# Sensor_Board.net
KiCad netlist of a schematic drawn in Altium Designer
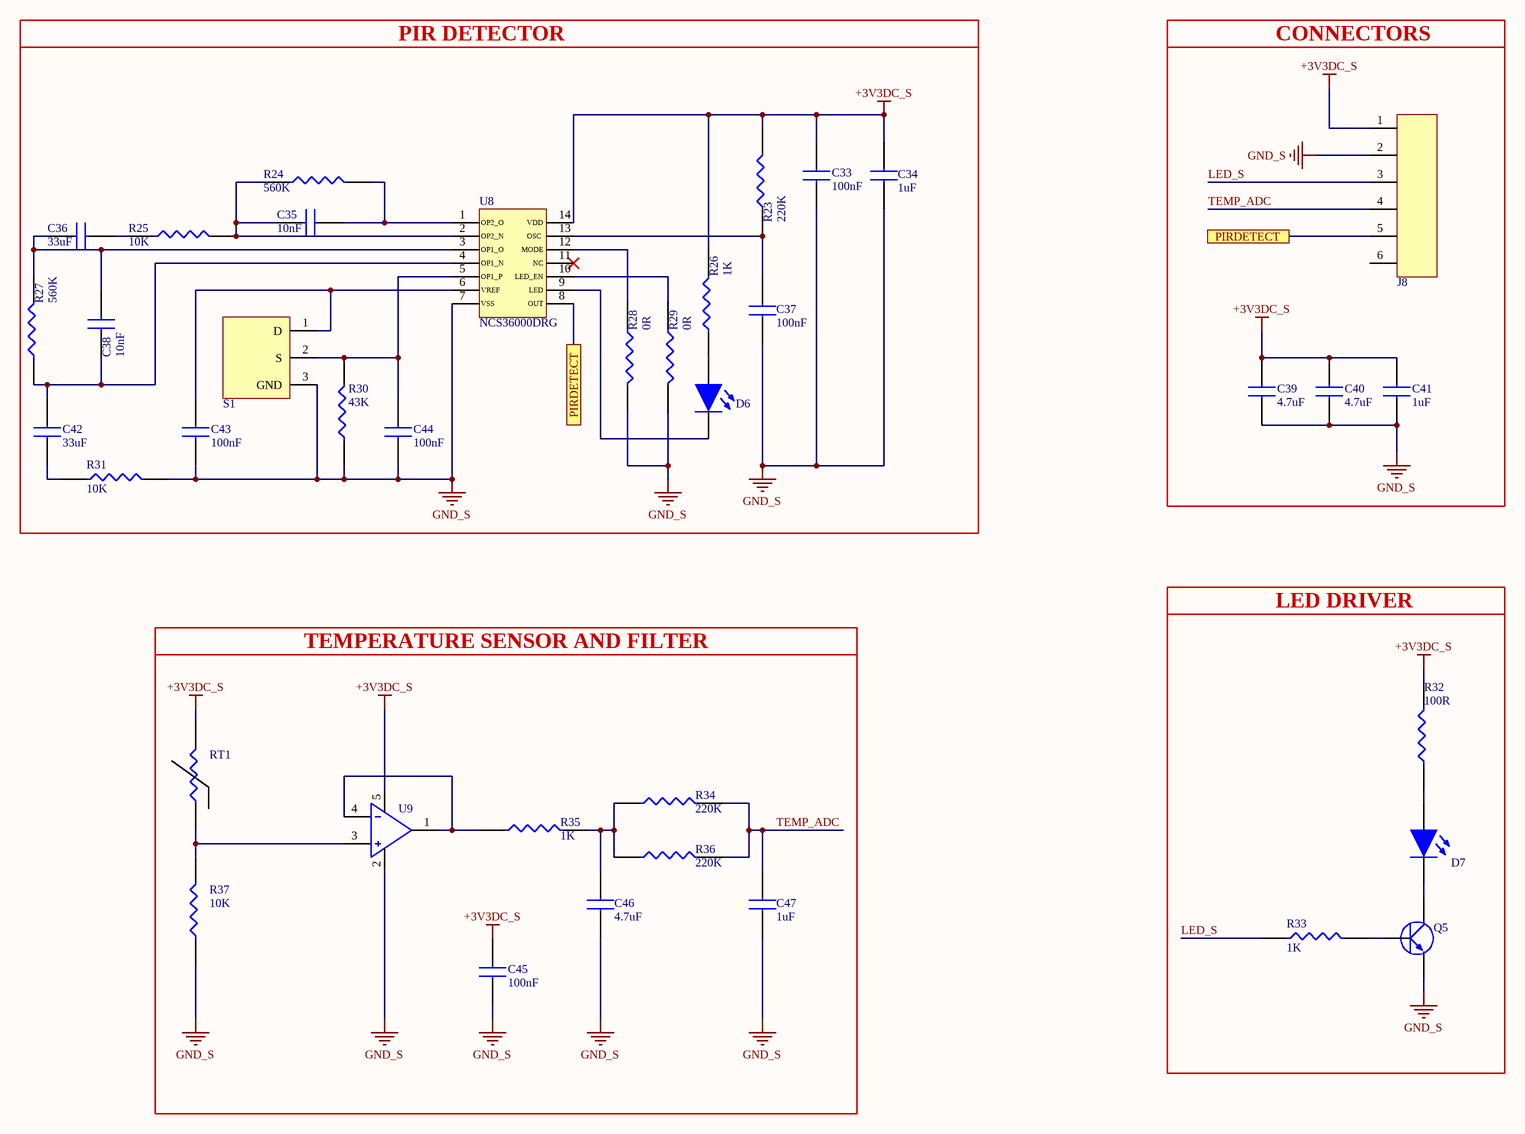
[diagram p0: Sensor Board.SchDoc]

(export (version "E")
  (design (tool "Eeschema 10.0.6"))
  (components
    (comp (ref "C33")
      (value "C0603C104K4RACTU")
      (footprint "CAP_0603")
      (description "Cap Cer 0.1uF 16V X7R 10% SMD 0603 125°C Paper T/R")
      (fields
        (field (name "MANUFACTURER") "KEMET")
        (field (name "TOLERANCE") "10%")
        (field (name "CAPACITANCE") "100nF")
        (field (name "DESIGNED BY") "Onur Karaduman")
      )
      (libsource (lib "Ders1Lib") (part "CAP CER 100nF 0603"))
    )
    (comp (ref "C34")
      (value "CL21B105KBFNNNE")
      (footprint "CAP_0805")
      (description "CAP CER 1UF 50V X7R 0805")
      (fields
        (field (name "MANUFACTURER") "Samsung")
        (field (name "TOLERANCE") "10%")
        (field (name "CAPACITANCE") "1uF")
        (field (name "DESIGNED BY") "Onur Karaduman")
      )
      (libsource (lib "Ders1Lib") (part "CAP CER 1uF 0805"))
    )
    (comp (ref "C35")
      (value "0603B103K160CT")
      (footprint "CAP_0603")
      (description "Multilayer Ceramic Capacitor, 0.01 F, 10%, X7R, 16 V, 0603 [1608 Metric] RoHS Compliant: Yes")
      (fields
        (field (name "MANUFACTURER") "Walsin Technologies")
        (field (name "TOLERANCE") "10%")
        (field (name "CAPACITANCE") "10nF")
        (field (name "DESIGNED BY") "Onur Karaduman")
      )
      (libsource (lib "Ders1Lib") (part "CAP CER 10nF 0603"))
    )
    (comp (ref "C36")
      (value "C3216X5R1E336M160AC")
      (footprint "CAP_1206")
      (description "C Series 1206 33 uF 25 V ±20 % Tolerance X5R SMT Multilayer Ceramic Capacitor")
      (fields
        (field (name "MANUFACTURER") "TDK")
        (field (name "TOLERANCE") "20%")
        (field (name "CAPACITANCE") "33uF")
        (field (name "DESIGNED BY") "Onur Karaduman")
      )
      (libsource (lib "Ders1Lib") (part "CAP CER 33uF 1206"))
    )
    (comp (ref "C37")
      (value "C0603C104K4RACTU")
      (footprint "CAP_0603")
      (description "Cap Cer 0.1uF 16V X7R 10% SMD 0603 125°C Paper T/R")
      (fields
        (field (name "MANUFACTURER") "KEMET")
        (field (name "TOLERANCE") "10%")
        (field (name "CAPACITANCE") "100nF")
        (field (name "DESIGNED BY") "Onur Karaduman")
      )
      (libsource (lib "Ders1Lib") (part "CAP CER 100nF 0603"))
    )
    (comp (ref "C38")
      (value "0603B103K160CT")
      (footprint "CAP_0603")
      (description "Multilayer Ceramic Capacitor, 0.01 F, 10%, X7R, 16 V, 0603 [1608 Metric] RoHS Compliant: Yes")
      (fields
        (field (name "MANUFACTURER") "Walsin Technologies")
        (field (name "TOLERANCE") "10%")
        (field (name "CAPACITANCE") "10nF")
        (field (name "DESIGNED BY") "Onur Karaduman")
      )
      (libsource (lib "Ders1Lib") (part "CAP CER 10nF 0603"))
    )
    (comp (ref "C39")
      (value "CL21A475KAQNNNE")
      (footprint "CAP_0805")
      (description "CAP CER 4.7UF 25V X5R 0805")
      (fields
        (field (name "MANUFACTURER") "Samsung")
        (field (name "TOLERANCE") "10%")
        (field (name "CAPACITANCE") "4.7uF")
        (field (name "DESIGNED BY") "Onur Karaduman")
      )
      (libsource (lib "Ders1Lib") (part "CAP CER 4.7uF 0805"))
    )
    (comp (ref "C40")
      (value "CL21A475KAQNNNE")
      (footprint "CAP_0805")
      (description "CAP CER 4.7UF 25V X5R 0805")
      (fields
        (field (name "MANUFACTURER") "Samsung")
        (field (name "TOLERANCE") "10%")
        (field (name "CAPACITANCE") "4.7uF")
        (field (name "DESIGNED BY") "Onur Karaduman")
      )
      (libsource (lib "Ders1Lib") (part "CAP CER 4.7uF 0805"))
    )
    (comp (ref "C41")
      (value "CL21B105KBFNNNE")
      (footprint "CAP_0805")
      (description "CAP CER 1UF 50V X7R 0805")
      (fields
        (field (name "MANUFACTURER") "Samsung")
        (field (name "TOLERANCE") "10%")
        (field (name "CAPACITANCE") "1uF")
        (field (name "DESIGNED BY") "Onur Karaduman")
      )
      (libsource (lib "Ders1Lib") (part "CAP CER 1uF 0805"))
    )
    (comp (ref "C42")
      (value "C3216X5R1E336M160AC")
      (footprint "CAP_1206")
      (description "C Series 1206 33 uF 25 V ±20 % Tolerance X5R SMT Multilayer Ceramic Capacitor")
      (fields
        (field (name "MANUFACTURER") "TDK")
        (field (name "TOLERANCE") "20%")
        (field (name "CAPACITANCE") "33uF")
        (field (name "DESIGNED BY") "Onur Karaduman")
      )
      (libsource (lib "Ders1Lib") (part "CAP CER 33uF 1206"))
    )
    (comp (ref "C43")
      (value "C0603C104K4RACTU")
      (footprint "CAP_0603")
      (description "Cap Cer 0.1uF 16V X7R 10% SMD 0603 125°C Paper T/R")
      (fields
        (field (name "MANUFACTURER") "KEMET")
        (field (name "TOLERANCE") "10%")
        (field (name "CAPACITANCE") "100nF")
        (field (name "DESIGNED BY") "Onur Karaduman")
      )
      (libsource (lib "Ders1Lib") (part "CAP CER 100nF 0603"))
    )
    (comp (ref "C44")
      (value "C0603C104K4RACTU")
      (footprint "CAP_0603")
      (description "Cap Cer 0.1uF 16V X7R 10% SMD 0603 125°C Paper T/R")
      (fields
        (field (name "MANUFACTURER") "KEMET")
        (field (name "TOLERANCE") "10%")
        (field (name "CAPACITANCE") "100nF")
        (field (name "DESIGNED BY") "Onur Karaduman")
      )
      (libsource (lib "Ders1Lib") (part "CAP CER 100nF 0603"))
    )
    (comp (ref "C45")
      (value "C0603C104K4RACTU")
      (footprint "CAP_0603")
      (description "Cap Cer 0.1uF 16V X7R 10% SMD 0603 125°C Paper T/R")
      (fields
        (field (name "MANUFACTURER") "KEMET")
        (field (name "TOLERANCE") "10%")
        (field (name "CAPACITANCE") "100nF")
        (field (name "DESIGNED BY") "Onur Karaduman")
      )
      (libsource (lib "Ders1Lib") (part "CAP CER 100nF 0603"))
    )
    (comp (ref "C46")
      (value "CL21A475KAQNNNE")
      (footprint "CAP_0805")
      (description "CAP CER 4.7UF 25V X5R 0805")
      (fields
        (field (name "MANUFACTURER") "Samsung")
        (field (name "TOLERANCE") "10%")
        (field (name "CAPACITANCE") "4.7uF")
        (field (name "DESIGNED BY") "Onur Karaduman")
      )
      (libsource (lib "Ders1Lib") (part "CAP CER 4.7uF 0805"))
    )
    (comp (ref "C47")
      (value "CL21B105KBFNNNE")
      (footprint "CAP_0805")
      (description "CAP CER 1UF 50V X7R 0805")
      (fields
        (field (name "MANUFACTURER") "Samsung")
        (field (name "TOLERANCE") "10%")
        (field (name "CAPACITANCE") "1uF")
        (field (name "DESIGNED BY") "Onur Karaduman")
      )
      (libsource (lib "Ders1Lib") (part "CAP CER 1uF 0805"))
    )
    (comp (ref "D6")
      (value "LTST-C171GKT")
      (footprint "LED_GREEN 0805")
      (description "Green 569nm LED Indication - Discrete 2.1V 0805 (2012 Metric)")
      (fields (field (name "MANUFACTURER") "Vishay Lite-On") (field (name "DESIGNED BY") "Onur Karaduman"))
      (libsource (lib "Ders1Lib") (part "LED GREEN 0805"))
    )
    (comp (ref "D7")
      (value "LH R974-LP-1")
      (footprint "LED_0805")
      (description "LED Uni-Color Hyper Red 660nm 2-Pin Chip 0805(2012Metric) T/R")
      (fields (field (name "MANUFACTURER") "Osram Opto") (field (name "DESIGNED BY") "Onur Karaduman"))
      (libsource (lib "Ders1Lib") (part "LED RED 0805"))
    )
    (comp (ref "J8")
      (value "64800611622")
      (footprint "64800611622")
      (description "Conn, Header, 6POS, 1ROW, 1.5MM;")
      (fields (field (name "MANUFACTURER") "Wurth Electronics") (field (name "DESIGNED BY") "Onur Karaduman"))
      (libsource (lib "Ders1Lib") (part "64800611622"))
    )
    (comp (ref "Q5")
      (value "MMBT3904-7-F")
      (footprint "SOT23-F")
      (description "NPN Ic=200mA Vceo=40V hfe=100~300 fT=310MHz P=300mW SOT-23")
      (fields (field (name "MANUFACTURER") "Diodes Zetex") (field (name "DESIGNED BY") "Onur Karaduman"))
      (libsource (lib "Ders1Lib") (part "MMBT3904-7-F"))
    )
    (comp (ref "R23")
      (value "RC0603JR-07220KL")
      (footprint "RES_0603")
      (description "Res Thick Film 0603 220K Ohm 5% 0.1W(1/10W) ±100ppm/C Pad SMD T/R")
      (fields
        (field (name "MANUFACTURER") "Yageo")
        (field (name "TOLERANCE") "5%")
        (field (name "RESISTANCE") "220K")
        (field (name "DESIGNED BY") "Onur Karaduman")
      )
      (libsource (lib "Ders1Lib") (part "RES 220K OHM 0603"))
    )
    (comp (ref "R24")
      (value "RC0603JR-07560KL")
      (footprint "RES_0603")
      (description "Res Thick Film 0603 560K Ohm 5% 0.1W(1/10W) ±100ppm/C Molded SMD Paper T/R")
      (fields
        (field (name "MANUFACTURER") "Yageo")
        (field (name "TOLERANCE") "5%")
        (field (name "RESISTANCE") "560K")
        (field (name "DESIGNED BY") "Onur Karaduman")
      )
      (libsource (lib "Ders1Lib") (part "RES 560K KOHM 0603"))
    )
    (comp (ref "R25")
      (value "RC0603FR-0710KL")
      (footprint "RES_0603")
      (description "RES SMD 10K OHM 1% 1/10W 0603")
      (fields
        (field (name "MANUFACTURER") "Yageo")
        (field (name "TOLERANCE") "1%")
        (field (name "RESISTANCE") "10K")
        (field (name "DESIGNED BY") "Onur Karaduman")
      )
      (libsource (lib "Ders1Lib") (part "RES 10K OHM 0603"))
    )
    (comp (ref "R26")
      (value "RES 1K OHM 0603")
      (footprint "RES_0603")
      (description "Res Thick Film 0603 1K Ohm 1% 0.25W(1/4W) ±100ppm/°C Epoxy Resin Pad SMD Automotive T/R")
      (fields
        (field (name "MANUFACTURER") "Rohm")
        (field (name "MANUFACTURER PART NUMBER") "ESR03EZPF1001")
        (field (name "RESISTANCE") "1K")
        (field (name "DESIGNED BY") "Onur Karaduman")
      )
      (libsource (lib "Ders1Lib") (part "RES 1K OHM 0603"))
    )
    (comp (ref "R27")
      (value "RC0603JR-07560KL")
      (footprint "RES_0603")
      (description "Res Thick Film 0603 560K Ohm 5% 0.1W(1/10W) ±100ppm/C Molded SMD Paper T/R")
      (fields
        (field (name "MANUFACTURER") "Yageo")
        (field (name "TOLERANCE") "5%")
        (field (name "RESISTANCE") "560K")
        (field (name "DESIGNED BY") "Onur Karaduman")
      )
      (libsource (lib "Ders1Lib") (part "RES 560K KOHM 0603"))
    )
    (comp (ref "R28")
      (value "RES 0 OHM 0603")
      (footprint "RES_0603")
      (description "RES SMD 0 OHM JUMPER 1/10W 0603")
      (fields
        (field (name "MANUFACTURER") "Yageo")
        (field (name "MANUFACTURER PART NUMBER") "RC0603JR-070RL")
        (field (name "RESISTANCE") "0R")
        (field (name "DESIGNED BY") "Onur Karaduman")
      )
      (libsource (lib "Ders1Lib") (part "RES 0 OHM 0603"))
    )
    (comp (ref "R29")
      (value "RES 0 OHM 0603")
      (footprint "RES_0603")
      (description "RES SMD 0 OHM JUMPER 1/10W 0603")
      (fields
        (field (name "MANUFACTURER") "Yageo")
        (field (name "MANUFACTURER PART NUMBER") "RC0603JR-070RL")
        (field (name "RESISTANCE") "0R")
        (field (name "DESIGNED BY") "Onur Karaduman")
      )
      (libsource (lib "Ders1Lib") (part "RES 0 OHM 0603"))
    )
    (comp (ref "R30")
      (value "RC0603JR-0743KL")
      (footprint "RES_0603")
      (description "Res Thick Film 0603 43K Ohm 5% 0.1W(1/10W) ±100ppm/°C Pad SMD T/R")
      (fields
        (field (name "MANUFACTURER") "Yageo")
        (field (name "TOLERANCE") "5%")
        (field (name "RESISTANCE") "43K")
        (field (name "DESIGNED BY") "Onur Karaduman")
      )
      (libsource (lib "Ders1Lib") (part "RES 43K OHM 0603"))
    )
    (comp (ref "R31")
      (value "RC0603FR-0710KL")
      (footprint "RES_0603")
      (description "RES SMD 10K OHM 1% 1/10W 0603")
      (fields
        (field (name "MANUFACTURER") "Yageo")
        (field (name "TOLERANCE") "1%")
        (field (name "RESISTANCE") "10K")
        (field (name "DESIGNED BY") "Onur Karaduman")
      )
      (libsource (lib "Ders1Lib") (part "RES 10K OHM 0603"))
    )
    (comp (ref "R32")
      (value "RC0603JR-07100RL")
      (footprint "RES_0603")
      (description "Res Thick Film 0603 100 Ohm 5% 1/10W ±100ppm/°C Molded SMD SMD Paper T/R")
      (fields
        (field (name "MANUFACTURER") "Yageo")
        (field (name "TOLERANCE") "5%")
        (field (name "RESISTANCE") "100R")
        (field (name "DESIGNED BY") "Onur Karaduman")
      )
      (libsource (lib "Ders1Lib") (part "RES 100 OHM 0603"))
    )
    (comp (ref "R33")
      (value "RES 1K OHM 0603")
      (footprint "RES_0603")
      (description "Res Thick Film 0603 1K Ohm 1% 0.25W(1/4W) ±100ppm/°C Epoxy Resin Pad SMD Automotive T/R")
      (fields
        (field (name "MANUFACTURER") "Rohm")
        (field (name "MANUFACTURER PART NUMBER") "ESR03EZPF1001")
        (field (name "RESISTANCE") "1K")
        (field (name "DESIGNED BY") "Onur Karaduman")
      )
      (libsource (lib "Ders1Lib") (part "RES 1K OHM 0603"))
    )
    (comp (ref "R34")
      (value "RC0603JR-07220KL")
      (footprint "RES_0603")
      (description "Res Thick Film 0603 220K Ohm 5% 0.1W(1/10W) ±100ppm/C Pad SMD T/R")
      (fields
        (field (name "MANUFACTURER") "Yageo")
        (field (name "TOLERANCE") "5%")
        (field (name "RESISTANCE") "220K")
        (field (name "DESIGNED BY") "Onur Karaduman")
      )
      (libsource (lib "Ders1Lib") (part "RES 220K OHM 0603"))
    )
    (comp (ref "R35")
      (value "RES 1K OHM 0603")
      (footprint "RES_0603")
      (description "Res Thick Film 0603 1K Ohm 1% 0.25W(1/4W) ±100ppm/°C Epoxy Resin Pad SMD Automotive T/R")
      (fields
        (field (name "MANUFACTURER") "Rohm")
        (field (name "MANUFACTURER PART NUMBER") "ESR03EZPF1001")
        (field (name "RESISTANCE") "1K")
        (field (name "DESIGNED BY") "Onur Karaduman")
      )
      (libsource (lib "Ders1Lib") (part "RES 1K OHM 0603"))
    )
    (comp (ref "R36")
      (value "RC0603JR-07220KL")
      (footprint "RES_0603")
      (description "Res Thick Film 0603 220K Ohm 5% 0.1W(1/10W) ±100ppm/C Pad SMD T/R")
      (fields
        (field (name "MANUFACTURER") "Yageo")
        (field (name "TOLERANCE") "5%")
        (field (name "RESISTANCE") "220K")
        (field (name "DESIGNED BY") "Onur Karaduman")
      )
      (libsource (lib "Ders1Lib") (part "RES 220K OHM 0603"))
    )
    (comp (ref "R37")
      (value "RC0603FR-0710KL")
      (footprint "RES_0603")
      (description "RES SMD 10K OHM 1% 1/10W 0603")
      (fields
        (field (name "MANUFACTURER") "Yageo")
        (field (name "TOLERANCE") "1%")
        (field (name "RESISTANCE") "10K")
        (field (name "DESIGNED BY") "Onur Karaduman")
      )
      (libsource (lib "Ders1Lib") (part "RES 10K OHM 0603"))
    )
    (comp (ref "RT1")
      (value "TFPT1206L1002FM")
      (footprint "TFPT 1206")
      (description "Thermistor PTC 10K Ohm 1% 2-Pin 1206 Surface Mount Solder Pad T/R Automotive")
      (fields (field (name "MANUFACTURER") "Vishay Dale") (field (name "TOLERANCE") "1%"))
      (libsource (lib "Ders1Lib") (part "TFPT1206L1002FM"))
    )
    (comp (ref "S1")
      (value "LHI 878/ 3902")
      (footprint "LHI 878/ 3902")
      (description "Sensor PIR (Passive Infrared) TO-205AA, TO-5-3 Metal Can")
      (fields
        (field (name "MANUFACTURER") "Excelitas")
        (field (name "MANUFACTURER PART NUMBER") "LHI878/3902")
        (field (name "DESIGNED BY") "Onur Karaduman")
      )
      (libsource (lib "Ders1Lib") (part "LHI 878/ 3902"))
    )
    (comp (ref "U8")
      (value "NCS36000DRG")
      (footprint "SOIC 14")
      (description "NCS36000 Series Single 5.75V Passive Infrared Detector Controller (PIR) -SOIC-14")
      (fields (field (name "MANUFACTURER") "ON Semiconductor"))
      (libsource (lib "Ders1Lib") (part "NCS36000DRG"))
    )
    (comp (ref "U9")
      (value "OPA314AIDBVR")
      (footprint "SOT23-5")
      (description "IC OPAMP GP 3MHZ RRO SOT23-5")
      (fields
        (field (name "MANUFACTURER") "Texas Instruments")
        (field (name "DESIGNED  BY") "Onur Karaduman")
      )
      (libsource (lib "Ders1Lib") (part "OPA314AIDBVR"))
    )
  )
  (nets
    (net (code "1") (name "+3V3DC_S") (class "Default")
      (node (ref "C33") (pin "2") (pintype "passive"))
      (node (ref "C34") (pin "2") (pintype "passive"))
      (node (ref "C39") (pin "2") (pintype "passive"))
      (node (ref "C40") (pin "2") (pintype "passive"))
      (node (ref "C41") (pin "2") (pintype "passive"))
      (node (ref "C45") (pin "2") (pintype "passive"))
      (node (ref "J8") (pin "1") (pintype "passive"))
      (node (ref "R23") (pin "2") (pintype "passive"))
      (node (ref "R26") (pin "2") (pintype "passive"))
      (node (ref "R32") (pin "2") (pintype "passive"))
      (node (ref "RT1") (pin "2") (pintype "passive"))
      (node (ref "U8") (pin "14") (pinfunction "VDD_14") (pintype "passive"))
      (node (ref "U9") (pin "5") (pintype "passive"))
    )
    (net (code "2") (name "/LED_S") (class "Default")
      (node (ref "J8") (pin "3") (pintype "passive"))
      (node (ref "R33") (pin "1") (pintype "passive"))
    )
    (net (code "3") (name "/PIRDETECT") (class "Default")
      (node (ref "J8") (pin "5") (pintype "passive"))
      (node (ref "U8") (pin "8") (pinfunction "OUT_8") (pintype "passive"))
    )
    (net (code "4") (name "/TEMP_ADC") (class "Default")
      (node (ref "C47") (pin "2") (pintype "passive"))
      (node (ref "J8") (pin "4") (pintype "passive"))
      (node (ref "R34") (pin "2") (pintype "passive"))
      (node (ref "R36") (pin "2") (pintype "passive"))
    )
    (net (code "5") (name "GND_S") (class "Default")
      (node (ref "C33") (pin "1") (pintype "passive"))
      (node (ref "C34") (pin "1") (pintype "passive"))
      (node (ref "C37") (pin "1") (pintype "passive"))
      (node (ref "C39") (pin "1") (pintype "passive"))
      (node (ref "C40") (pin "1") (pintype "passive"))
      (node (ref "C41") (pin "1") (pintype "passive"))
      (node (ref "C43") (pin "1") (pintype "passive"))
      (node (ref "C44") (pin "1") (pintype "passive"))
      (node (ref "C45") (pin "1") (pintype "passive"))
      (node (ref "C46") (pin "1") (pintype "passive"))
      (node (ref "C47") (pin "1") (pintype "passive"))
      (node (ref "J8") (pin "2") (pintype "passive"))
      (node (ref "Q5") (pin "2") (pinfunction "2_2") (pintype "passive"))
      (node (ref "R28") (pin "2") (pintype "passive"))
      (node (ref "R29") (pin "2") (pintype "passive"))
      (node (ref "R30") (pin "1") (pintype "passive"))
      (node (ref "R31") (pin "2") (pintype "passive"))
      (node (ref "R37") (pin "1") (pintype "passive"))
      (node (ref "S1") (pin "3") (pinfunction "GND_3") (pintype "passive"))
      (node (ref "U8") (pin "7") (pinfunction "VSS_7") (pintype "passive"))
      (node (ref "U9") (pin "2") (pintype "passive"))
    )
    (net (code "6") (name "Net-(C36-Pad2)") (class "Default")
      (node (ref "C36") (pin "2") (pintype "passive"))
      (node (ref "R25") (pin "1") (pintype "passive"))
    )
    (net (code "7") (name "Net-(C42-Pad1)") (class "Default")
      (node (ref "C42") (pin "1") (pintype "passive"))
      (node (ref "R31") (pin "1") (pintype "passive"))
    )
    (net (code "8") (name "Net-(C46-Pad2)") (class "Default")
      (node (ref "C46") (pin "2") (pintype "passive"))
      (node (ref "R34") (pin "1") (pintype "passive"))
      (node (ref "R35") (pin "2") (pintype "passive"))
      (node (ref "R36") (pin "1") (pintype "passive"))
    )
    (net (code "9") (name "Net-(D6-Pad1)") (class "Default")
      (node (ref "D6") (pin "1") (pintype "passive"))
      (node (ref "R26") (pin "1") (pintype "passive"))
    )
    (net (code "10") (name "Net-(D7-Pad1)") (class "Default")
      (node (ref "D7") (pin "1") (pinfunction "1_1") (pintype "passive"))
      (node (ref "R32") (pin "1") (pintype "passive"))
    )
    (net (code "11") (name "Net-(Q5-Pad1)") (class "Default")
      (node (ref "Q5") (pin "1") (pinfunction "1_1") (pintype "passive"))
      (node (ref "R33") (pin "2") (pintype "passive"))
    )
    (net (code "12") (name "Net-(Q5-_3)") (class "Default")
      (node (ref "D7") (pin "2") (pinfunction "2_2") (pintype "passive"))
      (node (ref "Q5") (pin "3") (pinfunction "_3_3") (pintype "passive"))
    )
    (net (code "13") (name "Net-(R35-Pad1)") (class "Default")
      (node (ref "R35") (pin "1") (pintype "passive"))
      (node (ref "U9") (pin "1") (pintype "passive"))
      (node (ref "U9") (pin "4") (pintype "passive"))
    )
    (net (code "14") (name "Net-(R37-Pad2)") (class "Default")
      (node (ref "R37") (pin "2") (pintype "passive"))
      (node (ref "RT1") (pin "1") (pintype "passive"))
      (node (ref "U9") (pin "3") (pintype "passive"))
    )
    (net (code "15") (name "Net-(S1-D)") (class "Default")
      (node (ref "C43") (pin "2") (pintype "passive"))
      (node (ref "S1") (pin "1") (pinfunction "D_1") (pintype "passive"))
      (node (ref "U8") (pin "6") (pinfunction "VREF_6") (pintype "passive"))
    )
    (net (code "16") (name "Net-(S1-S)") (class "Default")
      (node (ref "C44") (pin "2") (pintype "passive"))
      (node (ref "R30") (pin "2") (pintype "passive"))
      (node (ref "S1") (pin "2") (pinfunction "S_2") (pintype "passive"))
      (node (ref "U8") (pin "5") (pinfunction "OP1_P_5") (pintype "passive"))
    )
    (net (code "17") (name "Net-(U8-LED)") (class "Default")
      (node (ref "D6") (pin "2") (pintype "passive"))
      (node (ref "U8") (pin "9") (pinfunction "LED_9") (pintype "passive"))
    )
    (net (code "18") (name "Net-(U8-LED_EN)") (class "Default")
      (node (ref "R29") (pin "1") (pintype "passive"))
      (node (ref "U8") (pin "10") (pinfunction "LED_EN_10") (pintype "passive"))
    )
    (net (code "19") (name "Net-(U8-MODE)") (class "Default")
      (node (ref "R28") (pin "1") (pintype "passive"))
      (node (ref "U8") (pin "12") (pinfunction "MODE_12") (pintype "passive"))
    )
    (net (code "20") (name "Net-(U8-OP1_N)") (class "Default")
      (node (ref "C38") (pin "2") (pintype "passive"))
      (node (ref "C42") (pin "2") (pintype "passive"))
      (node (ref "R27") (pin "1") (pintype "passive"))
      (node (ref "U8") (pin "4") (pinfunction "OP1_N_4") (pintype "passive"))
    )
    (net (code "21") (name "Net-(U8-OP1_O)") (class "Default")
      (node (ref "C36") (pin "1") (pintype "passive"))
      (node (ref "C38") (pin "1") (pintype "passive"))
      (node (ref "R27") (pin "2") (pintype "passive"))
      (node (ref "U8") (pin "3") (pinfunction "OP1_O_3") (pintype "passive"))
    )
    (net (code "22") (name "Net-(U8-OP2_N)") (class "Default")
      (node (ref "C35") (pin "1") (pintype "passive"))
      (node (ref "R24") (pin "1") (pintype "passive"))
      (node (ref "R25") (pin "2") (pintype "passive"))
      (node (ref "U8") (pin "2") (pinfunction "OP2_N_2") (pintype "passive"))
    )
    (net (code "23") (name "Net-(U8-OP2_O)") (class "Default")
      (node (ref "C35") (pin "2") (pintype "passive"))
      (node (ref "R24") (pin "2") (pintype "passive"))
      (node (ref "U8") (pin "1") (pinfunction "OP2_O_1") (pintype "passive"))
    )
    (net (code "24") (name "Net-(U8-OSC)") (class "Default")
      (node (ref "C37") (pin "2") (pintype "passive"))
      (node (ref "R23") (pin "1") (pintype "passive"))
      (node (ref "U8") (pin "13") (pinfunction "OSC_13") (pintype "passive"))
    )
    (net (code "25") (name "unconnected-(J8-Pad6)") (class "Default")
      (node (ref "J8") (pin "6") (pintype "passive"))
    )
    (net (code "26") (name "unconnected-(U8-NC-Pad11)") (class "Default")
      (node (ref "U8") (pin "11") (pinfunction "NC_11") (pintype "passive+no_connect"))
    )
  )
)
